# FTDI.net
KiCad netlist of a schematic drawn in Altium Designer
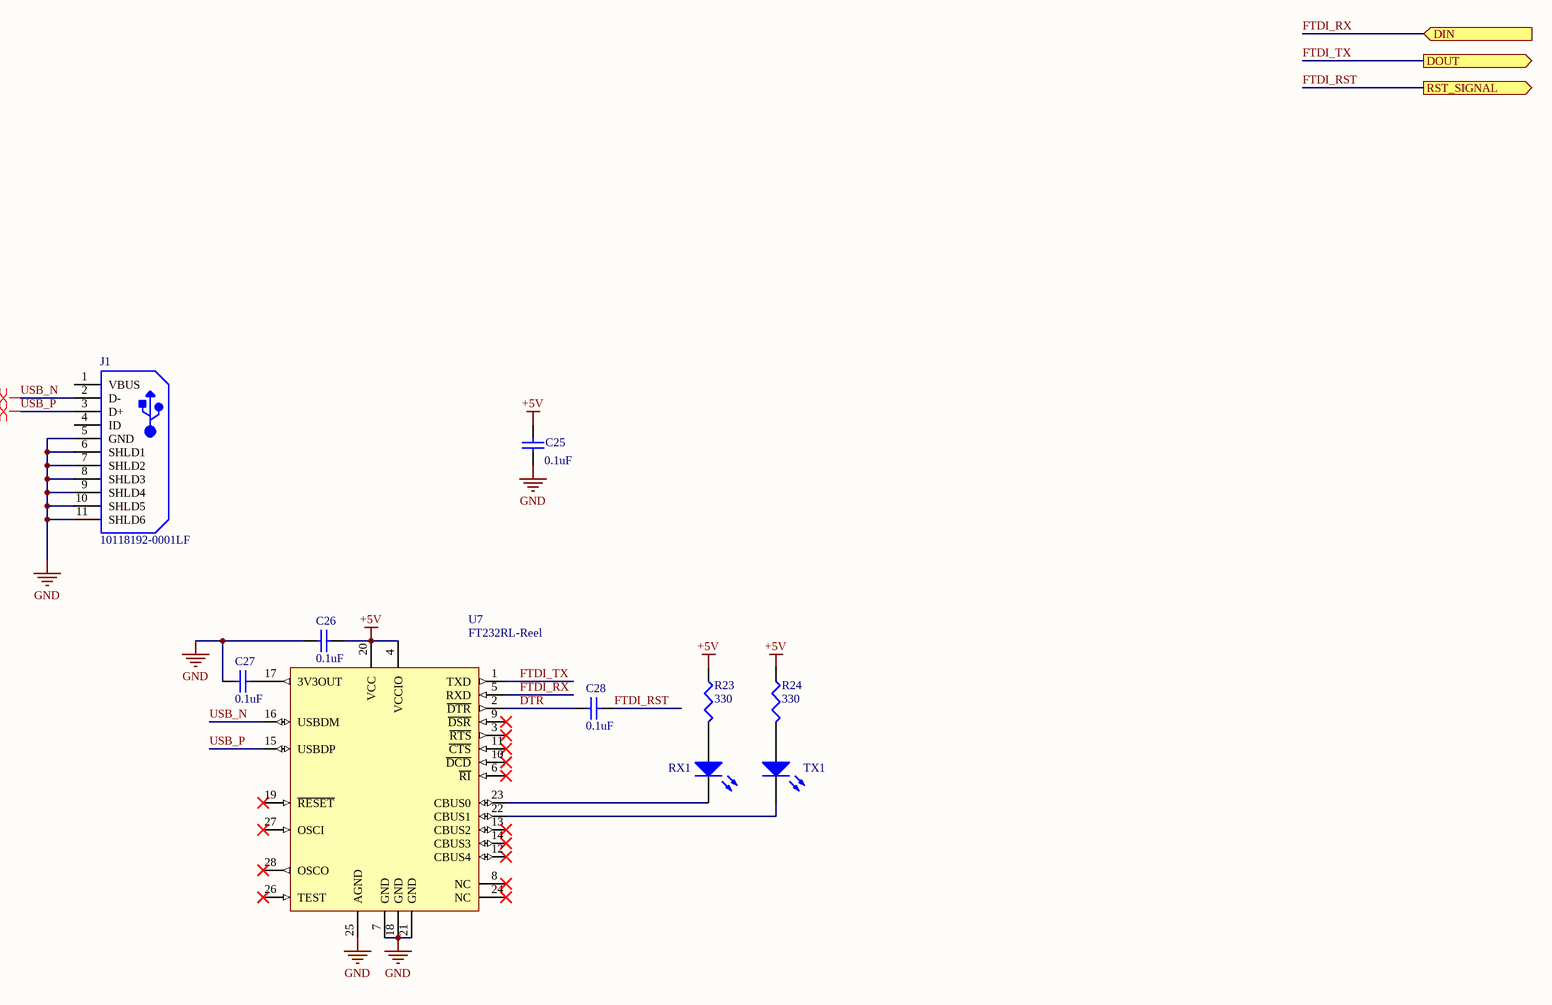
[diagram p0: FTDI.SchDoc]

(export (version "E")
  (design (tool "Eeschema 10.0.6"))
  (components
    (comp (ref "C25")
      (value "0.1uF")
      (footprint "1608[0603]")
      (description "Capacitor (Semiconductor SIM Model)")
      (fields (field (name "Comment") "Cap Semi") (field (name "PUBLISHER") "Altium Limited"))
      (libsource (lib "Miscellaneous Devices") (part "Cap Semi"))
    )
    (comp (ref "C26")
      (value "0.1uF")
      (footprint "1608[0603]")
      (description "Capacitor (Semiconductor SIM Model)")
      (fields (field (name "Comment") "Cap Semi") (field (name "PUBLISHER") "Altium Limited"))
      (libsource (lib "Miscellaneous Devices") (part "Cap Semi"))
    )
    (comp (ref "C27")
      (value "0.1uF")
      (footprint "1608[0603]")
      (description "Capacitor (Semiconductor SIM Model)")
      (fields (field (name "Comment") "Cap Semi") (field (name "PUBLISHER") "Altium Limited"))
      (libsource (lib "Miscellaneous Devices") (part "Cap Semi"))
    )
    (comp (ref "C28")
      (value "0.1uF")
      (footprint "1608[0603]")
      (description "Capacitor (Semiconductor SIM Model)")
      (fields (field (name "Comment") "Cap Semi") (field (name "PUBLISHER") "Altium Limited"))
      (libsource (lib "Miscellaneous Devices") (part "Cap Semi"))
    )
    (comp (ref "J1")
      (value "10118192-0001LF")
      (footprint "FCI-10118192-0001LF-5_V")
      (description "Micro USB B Type Receptacle, -55 to 85 degC, 5-Pin SMD, RoHS, Tape and Reel")
      (fields (field (name "MANUFACTURER") "FCI"))
      (libsource (lib "Altium Content Vault") (part "USB-5-6SHLD"))
    )
    (comp (ref "R23")
      (value "330")
      (footprint "J1-0603")
      (description "Resistor")
      (fields (field (name "Comment") "Res3") (field (name "PUBLISHER") "Altium Limited"))
      (libsource (lib "Miscellaneous Devices") (part "Res3"))
    )
    (comp (ref "R24")
      (value "330")
      (footprint "J1-0603")
      (description "Resistor")
      (fields (field (name "Comment") "Res3") (field (name "PUBLISHER") "Altium Limited"))
      (libsource (lib "Miscellaneous Devices") (part "Res3"))
    )
    (comp (ref "RX1")
      (value "150060RS75000")
      (footprint "0603_A")
      (description "SMD mono-color Chip LED, WL-SMCW, Red")
      (fields (field (name "MANUFACTURER") "Wuerth Elektronik"))
      (libsource (lib "Altium Content Vault") (part "CMP-1426-00001-1"))
    )
    (comp (ref "TX1")
      (value "150060RS75000")
      (footprint "0603_A")
      (description "SMD mono-color Chip LED, WL-SMCW, Red")
      (fields (field (name "MANUFACTURER") "Wuerth Elektronik"))
      (libsource (lib "Altium Content Vault") (part "CMP-1426-00001-1"))
    )
    (comp (ref "U7")
      (value "FT232RL-Reel")
      (footprint "SSOP-28_L")
      (description "USB UART Asynchronous Serial Data Transfer Chip, 28-pin SSOP, Tape and Reel")
      (fields (field (name "MANUFACTURER") "FTDI"))
      (libsource (lib "Altium Content Vault") (part "COM-UART-FT232R-IL28"))
    )
  )
  (nets
    (net (code "1") (name "+5V") (class "Default")
      (node (ref "C25") (pin "1") (pinfunction "1_1") (pintype "passive"))
      (node (ref "C26") (pin "2") (pinfunction "2_2") (pintype "passive"))
      (node (ref "R23") (pin "1") (pinfunction "1_1") (pintype "passive"))
      (node (ref "R24") (pin "1") (pinfunction "1_1") (pintype "passive"))
      (node (ref "U7") (pin "20") (pinfunction "VCC_20") (pintype "power_in"))
      (node (ref "U7") (pin "4") (pinfunction "VCCIO_4") (pintype "power_in"))
    )
    (net (code "2") (name "/DTR") (class "Default")
      (node (ref "C28") (pin "1") (pinfunction "1_1") (pintype "passive"))
      (node (ref "U7") (pin "2") (pinfunction "~{DTR}_2") (pintype "output"))
    )
    (net (code "3") (name "/FTDI_RST") (class "Default")
      (node (ref "C28") (pin "2") (pinfunction "2_2") (pintype "passive"))
    )
    (net (code "4") (name "/FTDI_RX") (class "Default")
      (node (ref "U7") (pin "5") (pinfunction "RXD_5") (pintype "input"))
    )
    (net (code "5") (name "/FTDI_TX") (class "Default")
      (node (ref "U7") (pin "1") (pinfunction "TXD_1") (pintype "output"))
    )
    (net (code "6") (name "/USB_N") (class "Default")
      (node (ref "J1") (pin "2") (pinfunction "D-_2") (pintype "passive"))
      (node (ref "U7") (pin "16") (pinfunction "USBDM_16") (pintype "bidirectional"))
    )
    (net (code "7") (name "/USB_P") (class "Default")
      (node (ref "J1") (pin "3") (pinfunction "D+_3") (pintype "passive"))
      (node (ref "U7") (pin "15") (pinfunction "USBDP_15") (pintype "bidirectional"))
    )
    (net (code "8") (name "GND") (class "Default")
      (node (ref "C25") (pin "2") (pinfunction "2_2") (pintype "passive"))
      (node (ref "C26") (pin "1") (pinfunction "1_1") (pintype "passive"))
      (node (ref "C27") (pin "1") (pinfunction "1_1") (pintype "passive"))
      (node (ref "J1") (pin "10") (pinfunction "SHLD5_10") (pintype "passive"))
      (node (ref "J1") (pin "11") (pinfunction "SHLD6_11") (pintype "passive"))
      (node (ref "J1") (pin "5") (pinfunction "GND_5") (pintype "passive"))
      (node (ref "J1") (pin "6") (pinfunction "SHLD1_6") (pintype "passive"))
      (node (ref "J1") (pin "7") (pinfunction "SHLD2_7") (pintype "passive"))
      (node (ref "J1") (pin "8") (pinfunction "SHLD3_8") (pintype "passive"))
      (node (ref "J1") (pin "9") (pinfunction "SHLD4_9") (pintype "passive"))
      (node (ref "U7") (pin "18") (pinfunction "GND_18") (pintype "power_in"))
      (node (ref "U7") (pin "21") (pinfunction "GND_21") (pintype "power_in"))
      (node (ref "U7") (pin "25") (pinfunction "AGND_25") (pintype "power_in"))
      (node (ref "U7") (pin "7") (pinfunction "GND_7") (pintype "power_in"))
    )
    (net (code "9") (name "Net-(RX1-A)") (class "Default")
      (node (ref "R23") (pin "2") (pinfunction "2_2") (pintype "passive"))
      (node (ref "RX1") (pin "2") (pinfunction "A_2") (pintype "passive"))
    )
    (net (code "10") (name "Net-(RX1-K)") (class "Default")
      (node (ref "RX1") (pin "1") (pinfunction "K_1") (pintype "passive"))
      (node (ref "U7") (pin "23") (pinfunction "CBUS0_23") (pintype "bidirectional"))
    )
    (net (code "11") (name "Net-(TX1-A)") (class "Default")
      (node (ref "R24") (pin "2") (pinfunction "2_2") (pintype "passive"))
      (node (ref "TX1") (pin "2") (pinfunction "A_2") (pintype "passive"))
    )
    (net (code "12") (name "Net-(TX1-K)") (class "Default")
      (node (ref "TX1") (pin "1") (pinfunction "K_1") (pintype "passive"))
      (node (ref "U7") (pin "22") (pinfunction "CBUS1_22") (pintype "bidirectional"))
    )
    (net (code "13") (name "Net-(U7-3V3OUT)") (class "Default")
      (node (ref "C27") (pin "2") (pinfunction "2_2") (pintype "passive"))
      (node (ref "U7") (pin "17") (pinfunction "3V3OUT_17") (pintype "output"))
    )
    (net (code "14") (name "unconnected-(J1-ID-Pad4)") (class "Default")
      (node (ref "J1") (pin "4") (pinfunction "ID_4") (pintype "passive"))
    )
    (net (code "15") (name "unconnected-(J1-VBUS-Pad1)") (class "Default")
      (node (ref "J1") (pin "1") (pinfunction "VBUS_1") (pintype "passive"))
    )
    (net (code "16") (name "unconnected-(U7-CBUS2-Pad13)") (class "Default")
      (node (ref "U7") (pin "13") (pinfunction "CBUS2_13") (pintype "bidirectional+no_connect"))
    )
    (net (code "17") (name "unconnected-(U7-CBUS3-Pad14)") (class "Default")
      (node (ref "U7") (pin "14") (pinfunction "CBUS3_14") (pintype "bidirectional+no_connect"))
    )
    (net (code "18") (name "unconnected-(U7-CBUS4-Pad12)") (class "Default")
      (node (ref "U7") (pin "12") (pinfunction "CBUS4_12") (pintype "bidirectional+no_connect"))
    )
    (net (code "19") (name "unconnected-(U7-NC-Pad8)") (class "Default")
      (node (ref "U7") (pin "8") (pinfunction "NC_8") (pintype "passive+no_connect"))
    )
    (net (code "20") (name "unconnected-(U7-NC-Pad24)") (class "Default")
      (node (ref "U7") (pin "24") (pinfunction "NC_24") (pintype "passive+no_connect"))
    )
    (net (code "21") (name "unconnected-(U7-OSCI-Pad27)") (class "Default")
      (node (ref "U7") (pin "27") (pinfunction "OSCI_27") (pintype "input+no_connect"))
    )
    (net (code "22") (name "unconnected-(U7-OSCO-Pad28)") (class "Default")
      (node (ref "U7") (pin "28") (pinfunction "OSCO_28") (pintype "output+no_connect"))
    )
    (net (code "23") (name "unconnected-(U7-TEST-Pad26)") (class "Default")
      (node (ref "U7") (pin "26") (pinfunction "TEST_26") (pintype "input+no_connect"))
    )
    (net (code "24") (name "unconnected-(U7-~{CTS}-Pad11)") (class "Default")
      (node (ref "U7") (pin "11") (pinfunction "~{CTS}_11") (pintype "input+no_connect"))
    )
    (net (code "25") (name "unconnected-(U7-~{DCD}-Pad10)") (class "Default")
      (node (ref "U7") (pin "10") (pinfunction "~{DCD}_10") (pintype "input+no_connect"))
    )
    (net (code "26") (name "unconnected-(U7-~{DSR}-Pad9)") (class "Default")
      (node (ref "U7") (pin "9") (pinfunction "~{DSR}_9") (pintype "input+no_connect"))
    )
    (net (code "27") (name "unconnected-(U7-~{RESET}-Pad19)") (class "Default")
      (node (ref "U7") (pin "19") (pinfunction "~{RESET}_19") (pintype "input+no_connect"))
    )
    (net (code "28") (name "unconnected-(U7-~{RI}-Pad6)") (class "Default")
      (node (ref "U7") (pin "6") (pinfunction "~{RI}_6") (pintype "input+no_connect"))
    )
    (net (code "29") (name "unconnected-(U7-~{RTS}-Pad3)") (class "Default")
      (node (ref "U7") (pin "3") (pinfunction "~{RTS}_3") (pintype "output+no_connect"))
    )
  )
)
